# MOD-Y_cold_V02.net
KiCad netlist of a schematic drawn in EAGLE
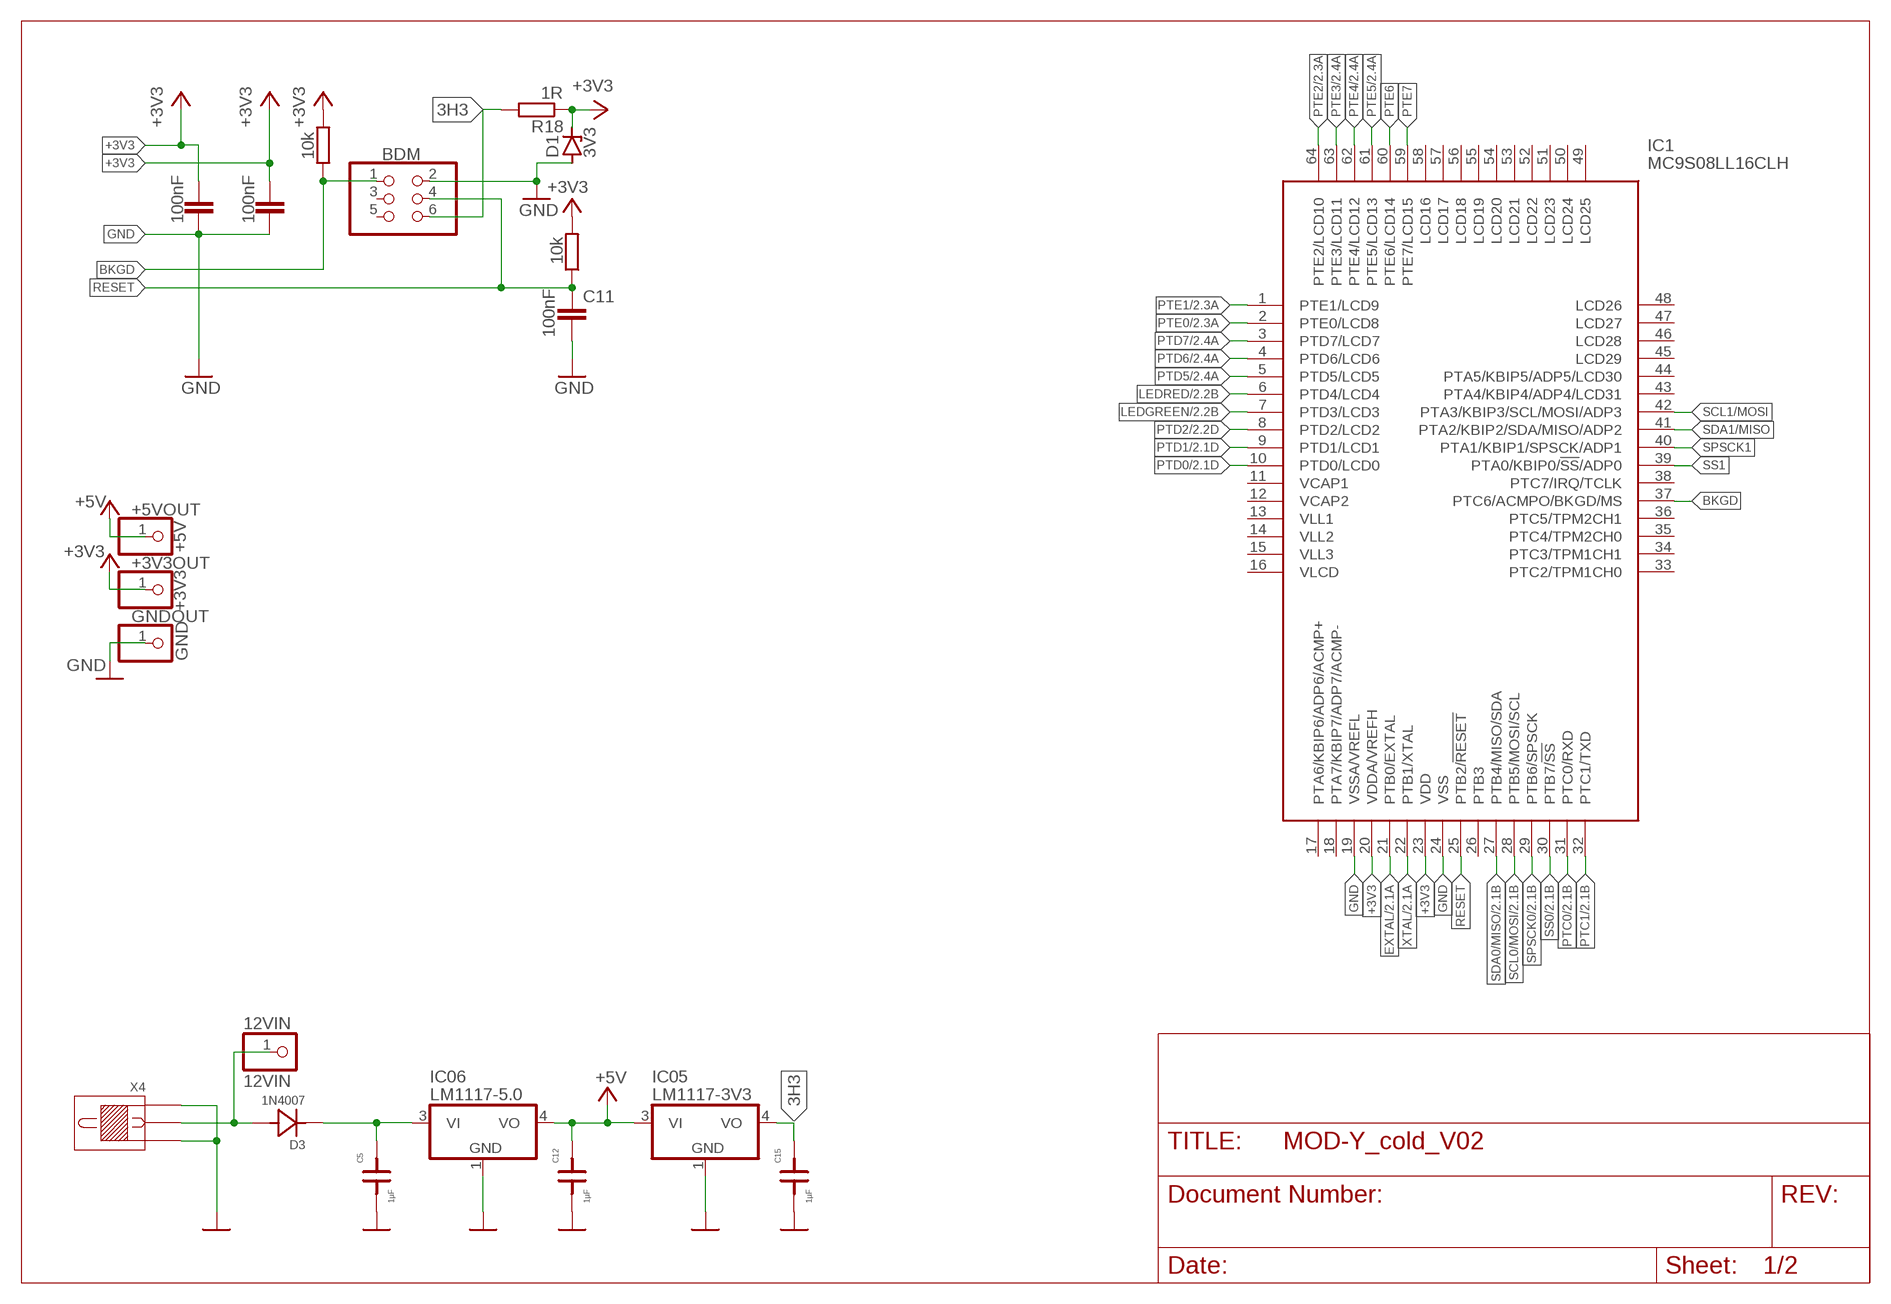
[diagram p0: schematic, sheet 1]
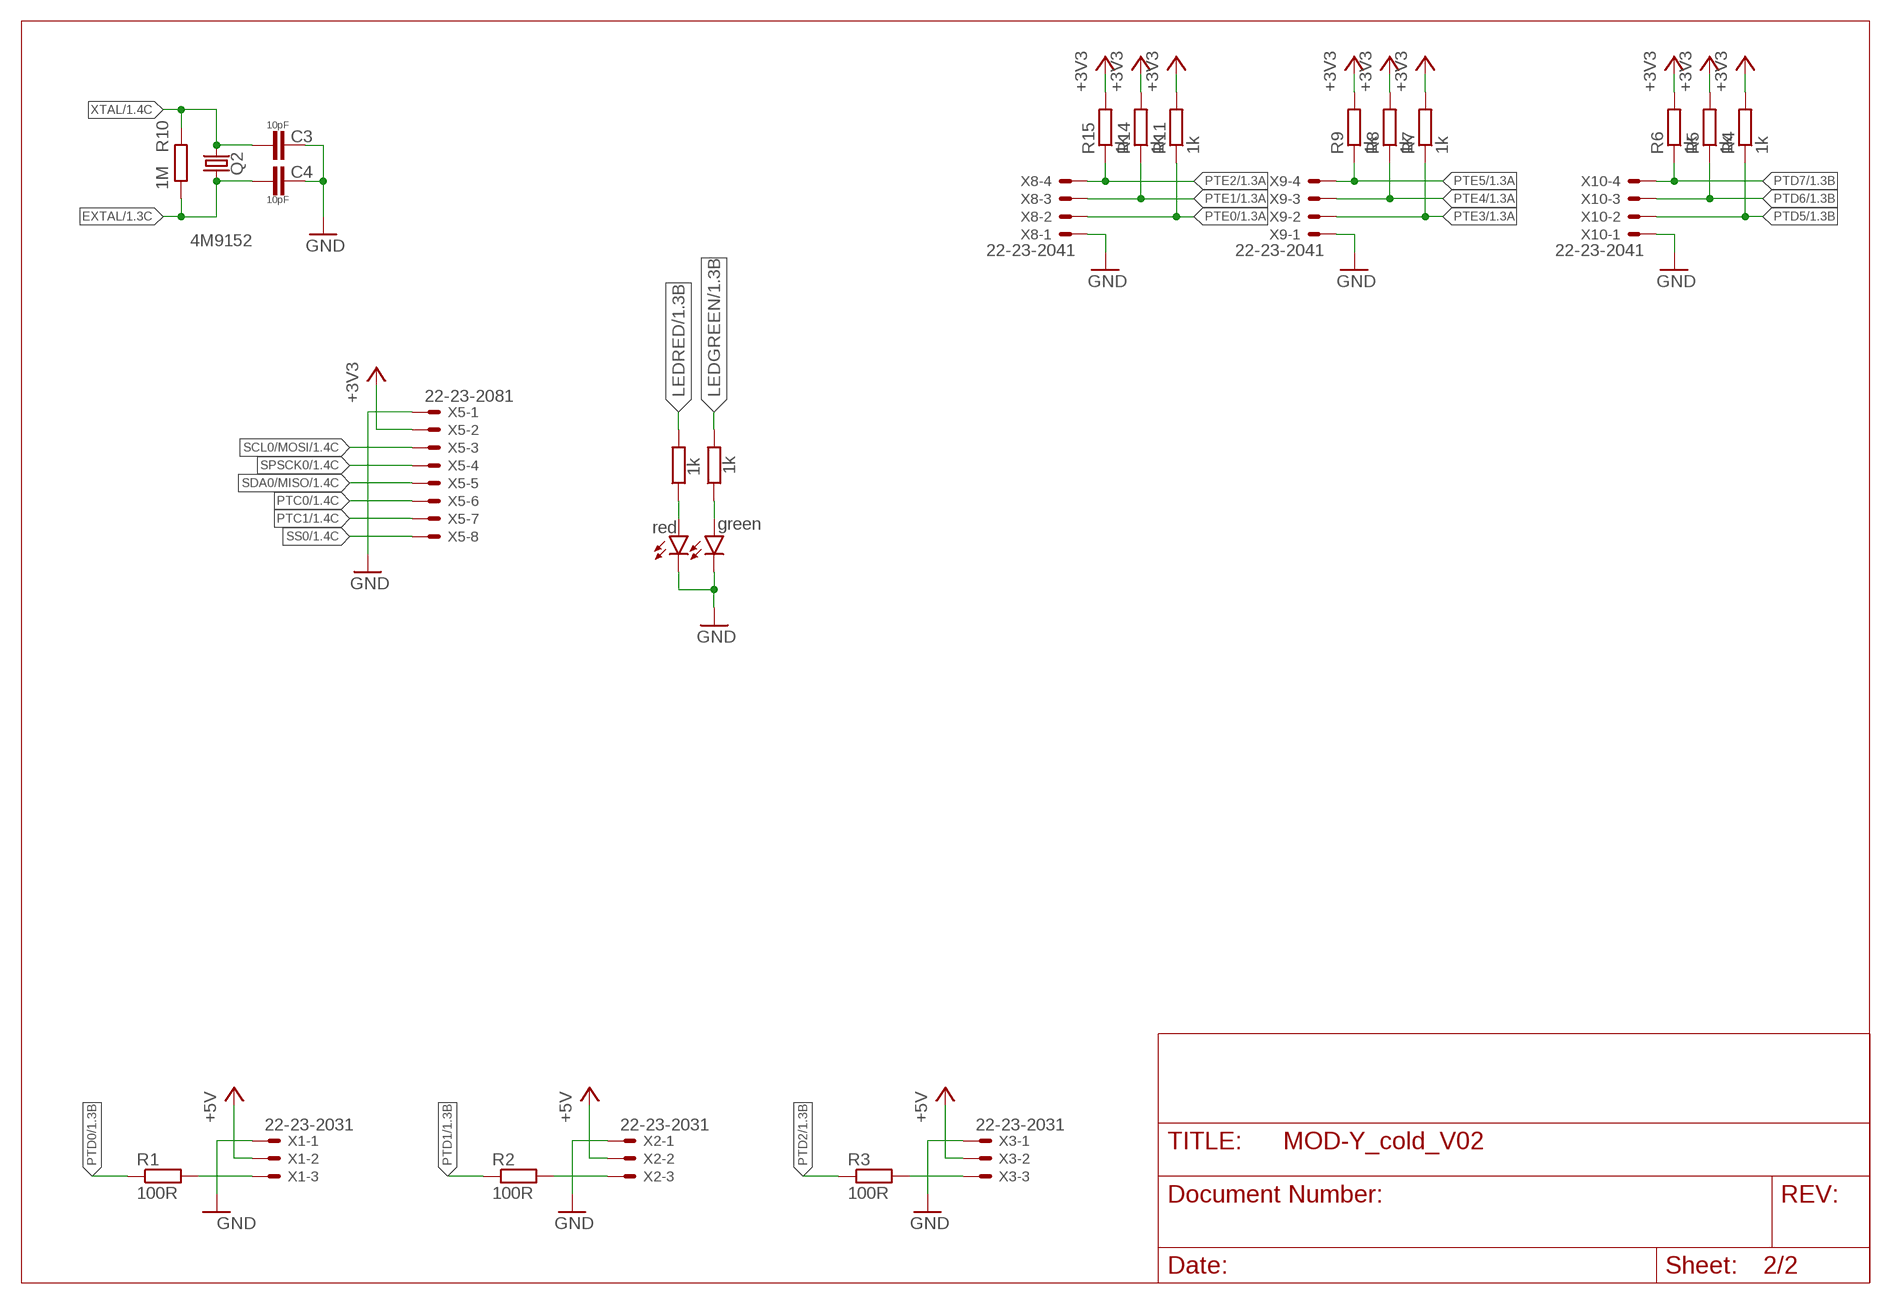
[diagram p1: schematic, sheet 2]

(export (version "E")
  (design (tool "Eeschema 10.0.6"))
  (components
    (comp (ref "+3V3OUT")
      (value "+3V3")
      (footprint "eagle-import:1X01")
      (libsource (lib "eagle-import") (part "PINHD-1X1"))
    )
    (comp (ref "+5VOUT")
      (value "+5V")
      (footprint "eagle-import:1X01")
      (libsource (lib "eagle-import") (part "PINHD-1X1"))
    )
    (comp (ref "12VIN")
      (value "12VIN")
      (footprint "eagle-import:1X01")
      (libsource (lib "eagle-import") (part "PINHD-1X1"))
    )
    (comp (ref "BDM")
      (value "PINHD-2X3")
      (footprint "eagle-import:2X03")
      (libsource (lib "eagle-import") (part "PINHD-2X3"))
    )
    (comp (ref "C5")
      (value "1µF")
      (footprint "eagle-import:0805F")
      (libsource (lib "eagle-import") (part "C1"))
    )
    (comp (ref "C9")
      (value "100nF")
      (footprint "eagle-import:C0805")
      (libsource (lib "eagle-import") (part "C-EUC0805"))
    )
    (comp (ref "C10")
      (value "100nF")
      (footprint "eagle-import:C0805")
      (libsource (lib "eagle-import") (part "C-EUC0805"))
    )
    (comp (ref "C11")
      (value "100nF")
      (footprint "eagle-import:C0805")
      (libsource (lib "eagle-import") (part "C-EUC0805"))
    )
    (comp (ref "C12")
      (value "1µF")
      (footprint "eagle-import:0805F")
      (libsource (lib "eagle-import") (part "C1"))
    )
    (comp (ref "C15")
      (value "1µF")
      (footprint "eagle-import:0805F")
      (libsource (lib "eagle-import") (part "C1"))
    )
    (comp (ref "D1")
      (value "3V3")
      (footprint "eagle-import:SOD80C")
      (libsource (lib "eagle-import") (part "ZENER-DIODESOD80C"))
    )
    (comp (ref "D3")
      (value "1N4007")
      (footprint "eagle-import:MELF_B")
      (libsource (lib "eagle-import") (part "DHCMELF"))
    )
    (comp (ref "GNDOUT")
      (value "GND")
      (footprint "eagle-import:1X01")
      (libsource (lib "eagle-import") (part "PINHD-1X1"))
    )
    (comp (ref "IC1")
      (value "MC9S08LL16CLH")
      (footprint "eagle-import:QFP50P1200X1200X160-64N")
      (fields (field (name "MOUSER_PART_NUMBER") "841-MC9S08LL16CLH"))
      (libsource (lib "eagle-import") (part "MC9S08LL16CLH"))
    )
    (comp (ref "IC05")
      (value "LM1117-3V3")
      (footprint "eagle-import:DPAK")
      (libsource (lib "eagle-import") (part "LM1117DT"))
    )
    (comp (ref "IC06")
      (value "LM1117-5.0")
      (footprint "eagle-import:DPAK")
      (libsource (lib "eagle-import") (part "LM1117DT"))
    )
    (comp (ref "R16")
      (value "10k")
      (footprint "eagle-import:R0805")
      (libsource (lib "eagle-import") (part "R-EU_R0805"))
    )
    (comp (ref "R17")
      (value "10k")
      (footprint "eagle-import:R0805")
      (libsource (lib "eagle-import") (part "R-EU_R0805"))
    )
    (comp (ref "R18")
      (value "1R")
      (footprint "eagle-import:R0805")
      (libsource (lib "eagle-import") (part "R-EU_R0805"))
    )
    (comp (ref "X4")
      (value "SPP")
      (footprint "eagle-import:SPP")
      (libsource (lib "eagle-import") (part "SPP"))
    )
    (comp (ref "C3")
      (value "10pF")
      (footprint "eagle-import:C0805")
      (libsource (lib "eagle-import") (part "C-EUC0805"))
    )
    (comp (ref "C4")
      (value "10pF")
      (footprint "eagle-import:C0805")
      (libsource (lib "eagle-import") (part "C-EUC0805"))
    )
    (comp (ref "LED1")
      (value "green")
      (footprint "eagle-import:CHIP-LED0805")
      (libsource (lib "eagle-import") (part "LEDCHIP-LED0805"))
    )
    (comp (ref "LED2")
      (value "red")
      (footprint "eagle-import:CHIP-LED0805")
      (libsource (lib "eagle-import") (part "LEDCHIP-LED0805"))
    )
    (comp (ref "Q2")
      (value "4M9152")
      (footprint "eagle-import:HC49UP")
      (libsource (lib "eagle-import") (part "CRYSTALHC49UP"))
    )
    (comp (ref "R1")
      (value "100R")
      (footprint "eagle-import:R0805")
      (libsource (lib "eagle-import") (part "R-EU_R0805"))
    )
    (comp (ref "R2")
      (value "100R")
      (footprint "eagle-import:R0805")
      (libsource (lib "eagle-import") (part "R-EU_R0805"))
    )
    (comp (ref "R3")
      (value "100R")
      (footprint "eagle-import:R0805")
      (libsource (lib "eagle-import") (part "R-EU_R0805"))
    )
    (comp (ref "R4")
      (value "1k")
      (footprint "eagle-import:R0805")
      (libsource (lib "eagle-import") (part "R-EU_R0805"))
    )
    (comp (ref "R5")
      (value "1k")
      (footprint "eagle-import:R0805")
      (libsource (lib "eagle-import") (part "R-EU_R0805"))
    )
    (comp (ref "R6")
      (value "1k")
      (footprint "eagle-import:R0805")
      (libsource (lib "eagle-import") (part "R-EU_R0805"))
    )
    (comp (ref "R7")
      (value "1k")
      (footprint "eagle-import:R0805")
      (libsource (lib "eagle-import") (part "R-EU_R0805"))
    )
    (comp (ref "R8")
      (value "1k")
      (footprint "eagle-import:R0805")
      (libsource (lib "eagle-import") (part "R-EU_R0805"))
    )
    (comp (ref "R9")
      (value "1k")
      (footprint "eagle-import:R0805")
      (libsource (lib "eagle-import") (part "R-EU_R0805"))
    )
    (comp (ref "R10")
      (value "1M")
      (footprint "eagle-import:R0805")
      (libsource (lib "eagle-import") (part "R-EU_R0805"))
    )
    (comp (ref "R11")
      (value "1k")
      (footprint "eagle-import:R0805")
      (libsource (lib "eagle-import") (part "R-EU_R0805"))
    )
    (comp (ref "R12")
      (value "1k")
      (footprint "eagle-import:R0805")
      (libsource (lib "eagle-import") (part "R-EU_R0805"))
    )
    (comp (ref "R13")
      (value "1k")
      (footprint "eagle-import:R0805")
      (libsource (lib "eagle-import") (part "R-EU_R0805"))
    )
    (comp (ref "R14")
      (value "1k")
      (footprint "eagle-import:R0805")
      (libsource (lib "eagle-import") (part "R-EU_R0805"))
    )
    (comp (ref "R15")
      (value "1k")
      (footprint "eagle-import:R0805")
      (libsource (lib "eagle-import") (part "R-EU_R0805"))
    )
    (comp (ref "X1")
      (value "22-23-2031")
      (footprint "eagle-import:22-23-2031")
      (fields (field (name "MF") "MOLEX"))
      (libsource (lib "eagle-import") (part "22-23-2031"))
    )
    (comp (ref "X2")
      (value "22-23-2031")
      (footprint "eagle-import:22-23-2031")
      (fields (field (name "MF") "MOLEX"))
      (libsource (lib "eagle-import") (part "22-23-2031"))
    )
    (comp (ref "X3")
      (value "22-23-2031")
      (footprint "eagle-import:22-23-2031")
      (fields (field (name "MF") "MOLEX"))
      (libsource (lib "eagle-import") (part "22-23-2031"))
    )
    (comp (ref "X5")
      (value "22-23-2081")
      (footprint "eagle-import:22-23-2081")
      (fields (field (name "MF") "MOLEX"))
      (libsource (lib "eagle-import") (part "22-23-2081"))
    )
    (comp (ref "X8")
      (value "22-23-2041")
      (footprint "eagle-import:22-23-2041")
      (fields (field (name "MF") "MOLEX"))
      (libsource (lib "eagle-import") (part "22-23-2041"))
    )
    (comp (ref "X9")
      (value "22-23-2041")
      (footprint "eagle-import:22-23-2041")
      (fields (field (name "MF") "MOLEX"))
      (libsource (lib "eagle-import") (part "22-23-2041"))
    )
    (comp (ref "X10")
      (value "22-23-2041")
      (footprint "eagle-import:22-23-2041")
      (fields (field (name "MF") "MOLEX"))
      (libsource (lib "eagle-import") (part "22-23-2041"))
    )
  )
  (nets
    (net (code "1") (name "+3V3") (class "Default")
      (node (ref "+3V3OUT") (pin "1") (pinfunction "1_1") (pintype "passive"))
      (node (ref "C10") (pin "1") (pinfunction "1_1") (pintype "passive"))
      (node (ref "C9") (pin "1") (pinfunction "1_1") (pintype "passive"))
      (node (ref "D1") (pin "C") (pinfunction "C_C") (pintype "passive"))
      (node (ref "IC1") (pin "20") (pinfunction "VDDA/VREFH_20") (pintype "bidirectional"))
      (node (ref "IC1") (pin "23") (pinfunction "VDD_23") (pintype "bidirectional"))
      (node (ref "R11") (pin "2") (pinfunction "2_2") (pintype "passive"))
      (node (ref "R14") (pin "2") (pinfunction "2_2") (pintype "passive"))
      (node (ref "R15") (pin "2") (pinfunction "2_2") (pintype "passive"))
      (node (ref "R16") (pin "2") (pinfunction "2_2") (pintype "passive"))
      (node (ref "R17") (pin "2") (pinfunction "2_2") (pintype "passive"))
      (node (ref "R18") (pin "1") (pinfunction "1_1") (pintype "passive"))
      (node (ref "R4") (pin "2") (pinfunction "2_2") (pintype "passive"))
      (node (ref "R5") (pin "2") (pinfunction "2_2") (pintype "passive"))
      (node (ref "R6") (pin "2") (pinfunction "2_2") (pintype "passive"))
      (node (ref "R7") (pin "2") (pinfunction "2_2") (pintype "passive"))
      (node (ref "R8") (pin "2") (pinfunction "2_2") (pintype "passive"))
      (node (ref "R9") (pin "2") (pinfunction "2_2") (pintype "passive"))
      (node (ref "X5") (pin "2") (pinfunction "S_2") (pintype "passive"))
    )
    (net (code "2") (name "+5V") (class "Default")
      (node (ref "+5VOUT") (pin "1") (pinfunction "1_1") (pintype "passive"))
      (node (ref "C12") (pin "2") (pinfunction "2_2") (pintype "bidirectional"))
      (node (ref "IC05") (pin "3") (pinfunction "VI_3") (pintype "input"))
      (node (ref "IC06") (pin "4") (pinfunction "VO_4") (pintype "output"))
      (node (ref "X1") (pin "2") (pinfunction "S_2") (pintype "passive"))
      (node (ref "X2") (pin "2") (pinfunction "S_2") (pintype "passive"))
      (node (ref "X3") (pin "2") (pinfunction "S_2") (pintype "passive"))
    )
    (net (code "3") (name "3H3") (class "Default")
      (node (ref "BDM") (pin "6") (pinfunction "6_6") (pintype "passive"))
      (node (ref "C15") (pin "2") (pinfunction "2_2") (pintype "bidirectional"))
      (node (ref "IC05") (pin "4") (pinfunction "VO_4") (pintype "output"))
      (node (ref "R18") (pin "2") (pinfunction "2_2") (pintype "passive"))
    )
    (net (code "4") (name "BKGD") (class "Default")
      (node (ref "BDM") (pin "1") (pinfunction "1_1") (pintype "passive"))
      (node (ref "IC1") (pin "37") (pinfunction "PTC6/ACMPO/BKGD/MS_37") (pintype "bidirectional"))
      (node (ref "R16") (pin "1") (pinfunction "1_1") (pintype "passive"))
    )
    (net (code "5") (name "EXTAL") (class "Default")
      (node (ref "C4") (pin "1") (pinfunction "1_1") (pintype "passive"))
      (node (ref "IC1") (pin "21") (pinfunction "PTB0/EXTAL_21") (pintype "bidirectional"))
      (node (ref "Q2") (pin "1") (pinfunction "1_1") (pintype "passive"))
      (node (ref "R10") (pin "1") (pinfunction "1_1") (pintype "passive"))
    )
    (net (code "6") (name "GND") (class "Default")
      (node (ref "BDM") (pin "2") (pinfunction "2_2") (pintype "passive"))
      (node (ref "C10") (pin "2") (pinfunction "2_2") (pintype "passive"))
      (node (ref "C11") (pin "2") (pinfunction "2_2") (pintype "passive"))
      (node (ref "C12") (pin "1") (pinfunction "1_1") (pintype "bidirectional"))
      (node (ref "C15") (pin "1") (pinfunction "1_1") (pintype "bidirectional"))
      (node (ref "C3") (pin "2") (pinfunction "2_2") (pintype "passive"))
      (node (ref "C4") (pin "2") (pinfunction "2_2") (pintype "passive"))
      (node (ref "C5") (pin "1") (pinfunction "1_1") (pintype "bidirectional"))
      (node (ref "C9") (pin "2") (pinfunction "2_2") (pintype "passive"))
      (node (ref "D1") (pin "A") (pinfunction "A_A") (pintype "passive"))
      (node (ref "GNDOUT") (pin "1") (pinfunction "1_1") (pintype "passive"))
      (node (ref "IC05") (pin "1") (pinfunction "GND_1") (pintype "input"))
      (node (ref "IC06") (pin "1") (pinfunction "GND_1") (pintype "input"))
      (node (ref "IC1") (pin "19") (pinfunction "VSSA/VREFL_19") (pintype "bidirectional"))
      (node (ref "IC1") (pin "24") (pinfunction "VSS_24") (pintype "bidirectional"))
      (node (ref "LED1") (pin "C") (pinfunction "C_C") (pintype "passive"))
      (node (ref "LED2") (pin "C") (pinfunction "C_C") (pintype "passive"))
      (node (ref "X1") (pin "1") (pinfunction "S_1") (pintype "passive"))
      (node (ref "X10") (pin "1") (pinfunction "S_1") (pintype "passive"))
      (node (ref "X2") (pin "1") (pinfunction "S_1") (pintype "passive"))
      (node (ref "X3") (pin "1") (pinfunction "S_1") (pintype "passive"))
      (node (ref "X4") (pin "1") (pinfunction "1_1") (pintype "bidirectional"))
      (node (ref "X4") (pin "3") (pinfunction "3_3") (pintype "bidirectional"))
      (node (ref "X5") (pin "1") (pinfunction "S_1") (pintype "passive"))
      (node (ref "X8") (pin "1") (pinfunction "S_1") (pintype "passive"))
      (node (ref "X9") (pin "1") (pinfunction "S_1") (pintype "passive"))
    )
    (net (code "7") (name "LEDGREEN") (class "Default")
      (node (ref "IC1") (pin "7") (pinfunction "PTD3/LCD3_7") (pintype "bidirectional"))
      (node (ref "R13") (pin "2") (pinfunction "2_2") (pintype "passive"))
    )
    (net (code "8") (name "LEDRED") (class "Default")
      (node (ref "IC1") (pin "6") (pinfunction "PTD4/LCD4_6") (pintype "bidirectional"))
      (node (ref "R12") (pin "2") (pinfunction "2_2") (pintype "passive"))
    )
    (net (code "9") (name "Net-(12VIN-Pad1)") (class "Default")
      (node (ref "12VIN") (pin "1") (pinfunction "1_1") (pintype "passive"))
      (node (ref "D3") (pin "A") (pinfunction "A_A") (pintype "bidirectional"))
      (node (ref "X4") (pin "2") (pinfunction "2_2") (pintype "bidirectional"))
    )
    (net (code "10") (name "Net-(IC06-VI)") (class "Default")
      (node (ref "C5") (pin "2") (pinfunction "2_2") (pintype "bidirectional"))
      (node (ref "D3") (pin "K") (pinfunction "K_K") (pintype "bidirectional"))
      (node (ref "IC06") (pin "3") (pinfunction "VI_3") (pintype "input"))
    )
    (net (code "11") (name "Net-(LED1-PadA)") (class "Default")
      (node (ref "LED1") (pin "A") (pinfunction "A_A") (pintype "passive"))
      (node (ref "R13") (pin "1") (pinfunction "1_1") (pintype "passive"))
    )
    (net (code "12") (name "Net-(LED2-PadA)") (class "Default")
      (node (ref "LED2") (pin "A") (pinfunction "A_A") (pintype "passive"))
      (node (ref "R12") (pin "1") (pinfunction "1_1") (pintype "passive"))
    )
    (net (code "13") (name "Net-(X1C-S)") (class "Default")
      (node (ref "R1") (pin "2") (pinfunction "2_2") (pintype "passive"))
      (node (ref "X1") (pin "3") (pinfunction "S_3") (pintype "passive"))
    )
    (net (code "14") (name "Net-(X2C-S)") (class "Default")
      (node (ref "R2") (pin "2") (pinfunction "2_2") (pintype "passive"))
      (node (ref "X2") (pin "3") (pinfunction "S_3") (pintype "passive"))
    )
    (net (code "15") (name "Net-(X3C-S)") (class "Default")
      (node (ref "R3") (pin "2") (pinfunction "2_2") (pintype "passive"))
      (node (ref "X3") (pin "3") (pinfunction "S_3") (pintype "passive"))
    )
    (net (code "16") (name "PTC0") (class "Default")
      (node (ref "IC1") (pin "31") (pinfunction "PTC0/RXD_31") (pintype "bidirectional"))
      (node (ref "X5") (pin "6") (pinfunction "S_6") (pintype "passive"))
    )
    (net (code "17") (name "PTC1") (class "Default")
      (node (ref "IC1") (pin "32") (pinfunction "PTC1/TXD_32") (pintype "bidirectional"))
      (node (ref "X5") (pin "7") (pinfunction "S_7") (pintype "passive"))
    )
    (net (code "18") (name "PTD0") (class "Default")
      (node (ref "IC1") (pin "10") (pinfunction "PTD0/LCD0_10") (pintype "bidirectional"))
      (node (ref "R1") (pin "1") (pinfunction "1_1") (pintype "passive"))
    )
    (net (code "19") (name "PTD1") (class "Default")
      (node (ref "IC1") (pin "9") (pinfunction "PTD1/LCD1_9") (pintype "bidirectional"))
      (node (ref "R2") (pin "1") (pinfunction "1_1") (pintype "passive"))
    )
    (net (code "20") (name "PTD2") (class "Default")
      (node (ref "IC1") (pin "8") (pinfunction "PTD2/LCD2_8") (pintype "bidirectional"))
      (node (ref "R3") (pin "1") (pinfunction "1_1") (pintype "passive"))
    )
    (net (code "21") (name "PTD5") (class "Default")
      (node (ref "IC1") (pin "5") (pinfunction "PTD5/LCD5_5") (pintype "bidirectional"))
      (node (ref "R4") (pin "1") (pinfunction "1_1") (pintype "passive"))
      (node (ref "X10") (pin "2") (pinfunction "S_2") (pintype "passive"))
    )
    (net (code "22") (name "PTD6") (class "Default")
      (node (ref "IC1") (pin "4") (pinfunction "PTD6/LCD6_4") (pintype "bidirectional"))
      (node (ref "R5") (pin "1") (pinfunction "1_1") (pintype "passive"))
      (node (ref "X10") (pin "3") (pinfunction "S_3") (pintype "passive"))
    )
    (net (code "23") (name "PTD7") (class "Default")
      (node (ref "IC1") (pin "3") (pinfunction "PTD7/LCD7_3") (pintype "bidirectional"))
      (node (ref "R6") (pin "1") (pinfunction "1_1") (pintype "passive"))
      (node (ref "X10") (pin "4") (pinfunction "S_4") (pintype "passive"))
    )
    (net (code "24") (name "PTE0") (class "Default")
      (node (ref "IC1") (pin "2") (pinfunction "PTE0/LCD8_2") (pintype "bidirectional"))
      (node (ref "R11") (pin "1") (pinfunction "1_1") (pintype "passive"))
      (node (ref "X8") (pin "2") (pinfunction "S_2") (pintype "passive"))
    )
    (net (code "25") (name "PTE1") (class "Default")
      (node (ref "IC1") (pin "1") (pinfunction "PTE1/LCD9_1") (pintype "bidirectional"))
      (node (ref "R14") (pin "1") (pinfunction "1_1") (pintype "passive"))
      (node (ref "X8") (pin "3") (pinfunction "S_3") (pintype "passive"))
    )
    (net (code "26") (name "PTE2") (class "Default")
      (node (ref "IC1") (pin "64") (pinfunction "PTE2/LCD10_64") (pintype "bidirectional"))
      (node (ref "R15") (pin "1") (pinfunction "1_1") (pintype "passive"))
      (node (ref "X8") (pin "4") (pinfunction "S_4") (pintype "passive"))
    )
    (net (code "27") (name "PTE3") (class "Default")
      (node (ref "IC1") (pin "63") (pinfunction "PTE3/LCD11_63") (pintype "bidirectional"))
      (node (ref "R7") (pin "1") (pinfunction "1_1") (pintype "passive"))
      (node (ref "X9") (pin "2") (pinfunction "S_2") (pintype "passive"))
    )
    (net (code "28") (name "PTE4") (class "Default")
      (node (ref "IC1") (pin "62") (pinfunction "PTE4/LCD12_62") (pintype "bidirectional"))
      (node (ref "R8") (pin "1") (pinfunction "1_1") (pintype "passive"))
      (node (ref "X9") (pin "3") (pinfunction "S_3") (pintype "passive"))
    )
    (net (code "29") (name "PTE5") (class "Default")
      (node (ref "IC1") (pin "61") (pinfunction "PTE5/LCD13_61") (pintype "bidirectional"))
      (node (ref "R9") (pin "1") (pinfunction "1_1") (pintype "passive"))
      (node (ref "X9") (pin "4") (pinfunction "S_4") (pintype "passive"))
    )
    (net (code "30") (name "PTE6") (class "Default")
      (node (ref "IC1") (pin "60") (pinfunction "PTE6/LCD14_60") (pintype "bidirectional"))
    )
    (net (code "31") (name "PTE7") (class "Default")
      (node (ref "IC1") (pin "59") (pinfunction "PTE7/LCD15_59") (pintype "bidirectional"))
    )
    (net (code "32") (name "RESET") (class "Default")
      (node (ref "BDM") (pin "4") (pinfunction "4_4") (pintype "passive"))
      (node (ref "C11") (pin "1") (pinfunction "1_1") (pintype "passive"))
      (node (ref "IC1") (pin "25") (pinfunction "PTB2/~{RESET}_25") (pintype "bidirectional"))
      (node (ref "R17") (pin "1") (pinfunction "1_1") (pintype "passive"))
    )
    (net (code "33") (name "SCL0{slash}MOSI") (class "Default")
      (node (ref "IC1") (pin "28") (pinfunction "PTB5/MOSI/SCL_28") (pintype "bidirectional"))
      (node (ref "X5") (pin "3") (pinfunction "S_3") (pintype "passive"))
    )
    (net (code "34") (name "SCL1{slash}MOSI") (class "Default")
      (node (ref "IC1") (pin "42") (pinfunction "PTA3/KBIP3/SCL/MOSI/ADP3_42") (pintype "bidirectional"))
    )
    (net (code "35") (name "SDA0{slash}MISO") (class "Default")
      (node (ref "IC1") (pin "27") (pinfunction "PTB4/MISO/SDA_27") (pintype "bidirectional"))
      (node (ref "X5") (pin "5") (pinfunction "S_5") (pintype "passive"))
    )
    (net (code "36") (name "SDA1{slash}MISO") (class "Default")
      (node (ref "IC1") (pin "41") (pinfunction "PTA2/KBIP2/SDA/MISO/ADP2_41") (pintype "bidirectional"))
    )
    (net (code "37") (name "SPSCK0") (class "Default")
      (node (ref "IC1") (pin "29") (pinfunction "PTB6/SPSCK_29") (pintype "bidirectional"))
      (node (ref "X5") (pin "4") (pinfunction "S_4") (pintype "passive"))
    )
    (net (code "38") (name "SPSCK1") (class "Default")
      (node (ref "IC1") (pin "40") (pinfunction "PTA1/KBIP1/SPSCK/ADP1_40") (pintype "bidirectional"))
    )
    (net (code "39") (name "SS0") (class "Default")
      (node (ref "IC1") (pin "30") (pinfunction "PTB7/~{SS}_30") (pintype "bidirectional"))
      (node (ref "X5") (pin "8") (pinfunction "S_8") (pintype "passive"))
    )
    (net (code "40") (name "SS1") (class "Default")
      (node (ref "IC1") (pin "39") (pinfunction "PTA0/KBIP0/~{SS}/ADP0_39") (pintype "bidirectional"))
    )
    (net (code "41") (name "XTAL") (class "Default")
      (node (ref "C3") (pin "1") (pinfunction "1_1") (pintype "passive"))
      (node (ref "IC1") (pin "22") (pinfunction "PTB1/XTAL_22") (pintype "bidirectional"))
      (node (ref "Q2") (pin "2") (pinfunction "2_2") (pintype "passive"))
      (node (ref "R10") (pin "2") (pinfunction "2_2") (pintype "passive"))
    )
    (net (code "42") (name "unconnected-(BDM-Pad3)") (class "Default")
      (node (ref "BDM") (pin "3") (pinfunction "3_3") (pintype "passive"))
    )
    (net (code "43") (name "unconnected-(BDM-Pad5)") (class "Default")
      (node (ref "BDM") (pin "5") (pinfunction "5_5") (pintype "passive"))
    )
    (net (code "44") (name "unconnected-(IC1-LCD16-Pad58)") (class "Default")
      (node (ref "IC1") (pin "58") (pinfunction "LCD16_58") (pintype "bidirectional"))
    )
    (net (code "45") (name "unconnected-(IC1-LCD17-Pad57)") (class "Default")
      (node (ref "IC1") (pin "57") (pinfunction "LCD17_57") (pintype "bidirectional"))
    )
    (net (code "46") (name "unconnected-(IC1-LCD18-Pad56)") (class "Default")
      (node (ref "IC1") (pin "56") (pinfunction "LCD18_56") (pintype "bidirectional"))
    )
    (net (code "47") (name "unconnected-(IC1-LCD19-Pad55)") (class "Default")
      (node (ref "IC1") (pin "55") (pinfunction "LCD19_55") (pintype "bidirectional"))
    )
    (net (code "48") (name "unconnected-(IC1-LCD20-Pad54)") (class "Default")
      (node (ref "IC1") (pin "54") (pinfunction "LCD20_54") (pintype "bidirectional"))
    )
    (net (code "49") (name "unconnected-(IC1-LCD21-Pad53)") (class "Default")
      (node (ref "IC1") (pin "53") (pinfunction "LCD21_53") (pintype "bidirectional"))
    )
    (net (code "50") (name "unconnected-(IC1-LCD22-Pad52)") (class "Default")
      (node (ref "IC1") (pin "52") (pinfunction "LCD22_52") (pintype "bidirectional"))
    )
    (net (code "51") (name "unconnected-(IC1-LCD23-Pad51)") (class "Default")
      (node (ref "IC1") (pin "51") (pinfunction "LCD23_51") (pintype "bidirectional"))
    )
    (net (code "52") (name "unconnected-(IC1-LCD24-Pad50)") (class "Default")
      (node (ref "IC1") (pin "50") (pinfunction "LCD24_50") (pintype "bidirectional"))
    )
    (net (code "53") (name "unconnected-(IC1-LCD25-Pad49)") (class "Default")
      (node (ref "IC1") (pin "49") (pinfunction "LCD25_49") (pintype "bidirectional"))
    )
    (net (code "54") (name "unconnected-(IC1-LCD26-Pad48)") (class "Default")
      (node (ref "IC1") (pin "48") (pinfunction "LCD26_48") (pintype "bidirectional"))
    )
    (net (code "55") (name "unconnected-(IC1-LCD27-Pad47)") (class "Default")
      (node (ref "IC1") (pin "47") (pinfunction "LCD27_47") (pintype "bidirectional"))
    )
    (net (code "56") (name "unconnected-(IC1-LCD28-Pad46)") (class "Default")
      (node (ref "IC1") (pin "46") (pinfunction "LCD28_46") (pintype "bidirectional"))
    )
    (net (code "57") (name "unconnected-(IC1-LCD29-Pad45)") (class "Default")
      (node (ref "IC1") (pin "45") (pinfunction "LCD29_45") (pintype "bidirectional"))
    )
    (net (code "58") (name "unconnected-(IC1-PTA4{slash}KBIP4{slash}ADP4{slash}LCD31-Pad43)") (class "Default")
      (node (ref "IC1") (pin "43") (pinfunction "PTA4/KBIP4/ADP4/LCD31_43") (pintype "bidirectional"))
    )
    (net (code "59") (name "unconnected-(IC1-PTA5{slash}KBIP5{slash}ADP5{slash}LCD30-Pad44)") (class "Default")
      (node (ref "IC1") (pin "44") (pinfunction "PTA5/KBIP5/ADP5/LCD30_44") (pintype "bidirectional"))
    )
    (net (code "60") (name "unconnected-(IC1-PTA6{slash}KBIP6{slash}ADP6{slash}ACMP+-Pad17)") (class "Default")
      (node (ref "IC1") (pin "17") (pinfunction "PTA6/KBIP6/ADP6/ACMP+_17") (pintype "bidirectional"))
    )
    (net (code "61") (name "unconnected-(IC1-PTA7{slash}KBIP7{slash}ADP7{slash}ACMP--Pad18)") (class "Default")
      (node (ref "IC1") (pin "18") (pinfunction "PTA7/KBIP7/ADP7/ACMP-_18") (pintype "bidirectional"))
    )
    (net (code "62") (name "unconnected-(IC1-PTB3-Pad26)") (class "Default")
      (node (ref "IC1") (pin "26") (pinfunction "PTB3_26") (pintype "bidirectional"))
    )
    (net (code "63") (name "unconnected-(IC1-PTC2{slash}TPM1CH0-Pad33)") (class "Default")
      (node (ref "IC1") (pin "33") (pinfunction "PTC2/TPM1CH0_33") (pintype "bidirectional"))
    )
    (net (code "64") (name "unconnected-(IC1-PTC3{slash}TPM1CH1-Pad34)") (class "Default")
      (node (ref "IC1") (pin "34") (pinfunction "PTC3/TPM1CH1_34") (pintype "bidirectional"))
    )
    (net (code "65") (name "unconnected-(IC1-PTC4{slash}TPM2CH0-Pad35)") (class "Default")
      (node (ref "IC1") (pin "35") (pinfunction "PTC4/TPM2CH0_35") (pintype "bidirectional"))
    )
    (net (code "66") (name "unconnected-(IC1-PTC5{slash}TPM2CH1-Pad36)") (class "Default")
      (node (ref "IC1") (pin "36") (pinfunction "PTC5/TPM2CH1_36") (pintype "bidirectional"))
    )
    (net (code "67") (name "unconnected-(IC1-PTC7{slash}IRQ{slash}TCLK-Pad38)") (class "Default")
      (node (ref "IC1") (pin "38") (pinfunction "PTC7/IRQ/TCLK_38") (pintype "bidirectional"))
    )
    (net (code "68") (name "unconnected-(IC1-VCAP1-Pad11)") (class "Default")
      (node (ref "IC1") (pin "11") (pinfunction "VCAP1_11") (pintype "bidirectional"))
    )
    (net (code "69") (name "unconnected-(IC1-VCAP2-Pad12)") (class "Default")
      (node (ref "IC1") (pin "12") (pinfunction "VCAP2_12") (pintype "bidirectional"))
    )
    (net (code "70") (name "unconnected-(IC1-VLCD-Pad16)") (class "Default")
      (node (ref "IC1") (pin "16") (pinfunction "VLCD_16") (pintype "bidirectional"))
    )
    (net (code "71") (name "unconnected-(IC1-VLL1-Pad13)") (class "Default")
      (node (ref "IC1") (pin "13") (pinfunction "VLL1_13") (pintype "bidirectional"))
    )
    (net (code "72") (name "unconnected-(IC1-VLL2-Pad14)") (class "Default")
      (node (ref "IC1") (pin "14") (pinfunction "VLL2_14") (pintype "bidirectional"))
    )
    (net (code "73") (name "unconnected-(IC1-VLL3-Pad15)") (class "Default")
      (node (ref "IC1") (pin "15") (pinfunction "VLL3_15") (pintype "bidirectional"))
    )
  )
)
